# Receiver.net
KiCad netlist of a schematic drawn in Altium Designer
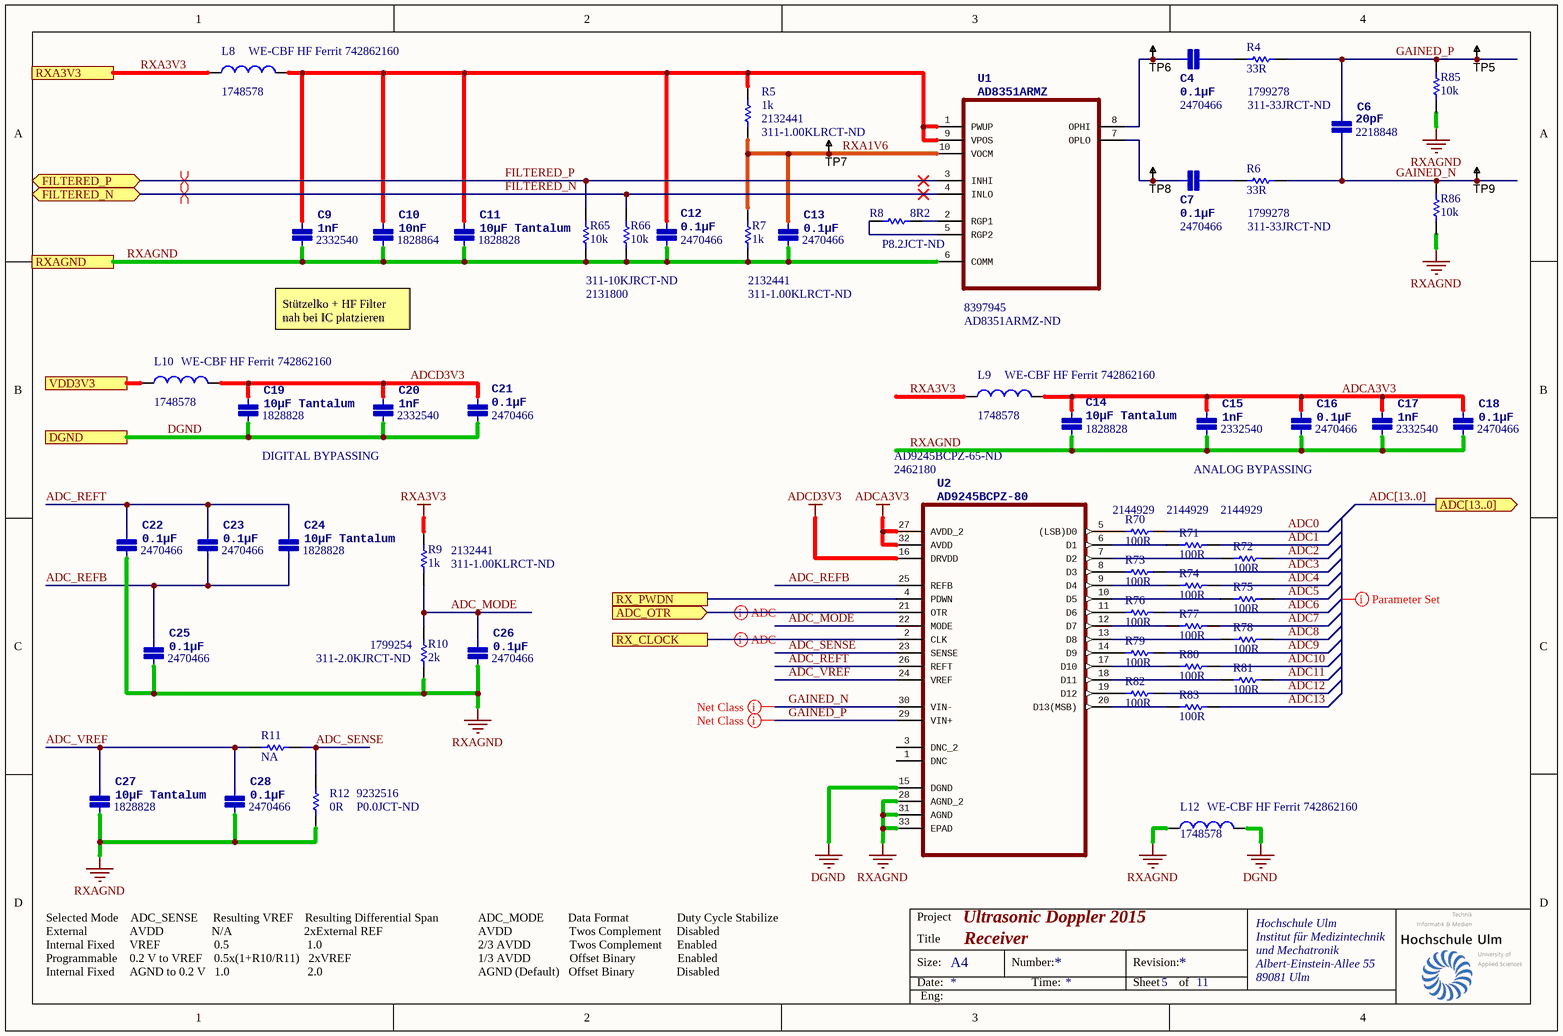
[diagram p0: Receiver.SchDoc]

(export (version "E")
  (design (tool "Eeschema 10.0.6"))
  (components
    (comp (ref "C4")
      (value "0.1µF")
      (footprint "0402[1005]")
      (description "Cap")
      (fields (field (name "SUPPLIER PART NUMBER 1") "2470466"))
      (libsource (lib "") (part "Capacitor_1"))
    )
    (comp (ref "C6")
      (value "20pF")
      (footprint "0402[1005]")
      (description "Cap")
      (fields (field (name "SUPPLIER PART NUMBER 1") "2218848"))
      (libsource (lib "Components") (part "Capacitor"))
    )
    (comp (ref "C7")
      (value "0.1µF")
      (footprint "0402[1005]")
      (description "Cap")
      (fields (field (name "SUPPLIER PART NUMBER 1") "2470466"))
      (libsource (lib "") (part "Capacitor_1"))
    )
    (comp (ref "C9")
      (value "1nF")
      (footprint "0402[1005]")
      (description "Cap")
      (fields (field (name "SUPPLIER PART NUMBER 1") "2332540"))
      (libsource (lib "Components") (part "Capacitor"))
    )
    (comp (ref "C10")
      (value "10nF")
      (footprint "0402[1005]")
      (description "Cap")
      (fields (field (name "SUPPLIER PART NUMBER 1") "1828864"))
      (libsource (lib "Components") (part "Capacitor"))
    )
    (comp (ref "C11")
      (value "10µF Tantalum")
      (footprint "0805[2012]")
      (description "Cap")
      (fields (field (name "SUPPLIER PART NUMBER 1") "1828828"))
      (libsource (lib "Components") (part "Capacitor"))
    )
    (comp (ref "C12")
      (value "0.1µF")
      (footprint "0402[1005]")
      (description "Cap")
      (fields (field (name "SUPPLIER PART NUMBER 1") "2470466"))
      (libsource (lib "Components") (part "Capacitor"))
    )
    (comp (ref "C13")
      (value "0.1µF")
      (footprint "0402[1005]")
      (description "Cap")
      (fields (field (name "SUPPLIER PART NUMBER 1") "2470466"))
      (libsource (lib "Components") (part "Capacitor"))
    )
    (comp (ref "C14")
      (value "10µF Tantalum")
      (footprint "0805[2012]")
      (description "Cap")
      (fields (field (name "SUPPLIER PART NUMBER 1") "1828828"))
      (libsource (lib "Components") (part "Capacitor"))
    )
    (comp (ref "C15")
      (value "1nF")
      (footprint "0402[1005]")
      (description "Cap")
      (fields (field (name "SUPPLIER PART NUMBER 1") "2332540"))
      (libsource (lib "Components") (part "Capacitor"))
    )
    (comp (ref "C16")
      (value "0.1µF")
      (footprint "0402[1005]")
      (description "Cap")
      (fields (field (name "SUPPLIER PART NUMBER 1") "2470466"))
      (libsource (lib "Components") (part "Capacitor"))
    )
    (comp (ref "C17")
      (value "1nF")
      (footprint "0402[1005]")
      (description "Cap")
      (fields (field (name "SUPPLIER PART NUMBER 1") "2332540"))
      (libsource (lib "Components") (part "Capacitor"))
    )
    (comp (ref "C18")
      (value "0.1µF")
      (footprint "0402[1005]")
      (description "Cap")
      (fields (field (name "SUPPLIER PART NUMBER 1") "2470466"))
      (libsource (lib "Components") (part "Capacitor"))
    )
    (comp (ref "C19")
      (value "10µF Tantalum")
      (footprint "0805[2012]")
      (description "Cap")
      (fields (field (name "SUPPLIER PART NUMBER 1") "1828828"))
      (libsource (lib "Components") (part "Capacitor"))
    )
    (comp (ref "C20")
      (value "1nF")
      (footprint "0402[1005]")
      (description "Cap")
      (fields (field (name "SUPPLIER PART NUMBER 1") "2332540"))
      (libsource (lib "Components") (part "Capacitor"))
    )
    (comp (ref "C21")
      (value "0.1µF")
      (footprint "0402[1005]")
      (description "Cap")
      (fields (field (name "SUPPLIER PART NUMBER 1") "2470466"))
      (libsource (lib "Components") (part "Capacitor"))
    )
    (comp (ref "C22")
      (value "0.1µF")
      (footprint "0402[1005]")
      (description "Cap")
      (fields (field (name "SUPPLIER PART NUMBER 1") "2470466"))
      (libsource (lib "Components") (part "Capacitor"))
    )
    (comp (ref "C23")
      (value "0.1µF")
      (footprint "0402[1005]")
      (description "Cap")
      (fields (field (name "SUPPLIER PART NUMBER 1") "2470466"))
      (libsource (lib "Components") (part "Capacitor"))
    )
    (comp (ref "C24")
      (value "10µF Tantalum")
      (footprint "0805[2012]")
      (description "Cap")
      (fields (field (name "SUPPLIER PART NUMBER 1") "1828828"))
      (libsource (lib "Components") (part "Capacitor"))
    )
    (comp (ref "C25")
      (value "0.1µF")
      (footprint "0402[1005]")
      (description "Cap")
      (fields (field (name "SUPPLIER PART NUMBER 1") "2470466"))
      (libsource (lib "Components") (part "Capacitor"))
    )
    (comp (ref "C26")
      (value "0.1µF")
      (footprint "0402[1005]")
      (description "Cap")
      (fields (field (name "SUPPLIER PART NUMBER 1") "2470466"))
      (libsource (lib "Components") (part "Capacitor"))
    )
    (comp (ref "C27")
      (value "10µF Tantalum")
      (footprint "0805[2012]")
      (description "Cap")
      (fields (field (name "SUPPLIER PART NUMBER 1") "1828828"))
      (libsource (lib "Components") (part "Capacitor"))
    )
    (comp (ref "C28")
      (value "0.1µF")
      (footprint "0402[1005]")
      (description "Cap")
      (fields (field (name "SUPPLIER PART NUMBER 1") "2470466"))
      (libsource (lib "Components") (part "Capacitor"))
    )
    (comp (ref "L8")
      (value "WE-CBF HF Ferrit 742862160")
      (footprint "0603[1508]")
      (description "Inductor")
      (fields (field (name "SUPPLIER PART NUMBER 1") "1748578") (field (name "PUBLISHER") "Altium Limited"))
      (libsource (lib "USD Parts") (part "Inductor"))
    )
    (comp (ref "L9")
      (value "WE-CBF HF Ferrit 742862160")
      (footprint "0603[1508]")
      (description "Inductor")
      (fields (field (name "SUPPLIER PART NUMBER 1") "1748578") (field (name "PUBLISHER") "Altium Limited"))
      (libsource (lib "USD Parts") (part "Inductor"))
    )
    (comp (ref "L10")
      (value "WE-CBF HF Ferrit 742862160")
      (footprint "0603[1508]")
      (description "Inductor")
      (fields (field (name "SUPPLIER PART NUMBER 1") "1748578") (field (name "PUBLISHER") "Altium Limited"))
      (libsource (lib "USD Parts") (part "Inductor"))
    )
    (comp (ref "L12")
      (value "WE-CBF HF Ferrit 742862160")
      (footprint "0603[1508]")
      (description "Inductor")
      (fields (field (name "SUPPLIER PART NUMBER 1") "1748578") (field (name "PUBLISHER") "Altium Limited"))
      (libsource (lib "USD Parts") (part "Inductor"))
    )
    (comp (ref "R4")
      (value "33R")
      (footprint "0402[1005]")
      (description "Resistor")
      (fields
        (field (name "SUPPLIER PART NUMBER 1") "311-33JRCT-ND")
        (field (name "SUPPLIER PART NUMBER 2") "1799278")
        (field (name "PUBLISHER") "Altium Limited")
      )
      (libsource (lib "Components") (part "Resistor"))
    )
    (comp (ref "R5")
      (value "1k")
      (footprint "0402[1005]")
      (description "Resistor")
      (fields
        (field (name "SUPPLIER PART NUMBER 1") "311-1.00KLRCT-ND")
        (field (name "SUPPLIER PART NUMBER 2") "2132441")
        (field (name "PUBLISHER") "Altium Limited")
      )
      (libsource (lib "Components") (part "Resistor"))
    )
    (comp (ref "R6")
      (value "33R")
      (footprint "0402[1005]")
      (description "Resistor")
      (fields
        (field (name "SUPPLIER PART NUMBER 1") "311-33JRCT-ND")
        (field (name "SUPPLIER PART NUMBER 2") "1799278")
        (field (name "PUBLISHER") "Altium Limited")
      )
      (libsource (lib "Components") (part "Resistor"))
    )
    (comp (ref "R7")
      (value "1k")
      (footprint "0402[1005]")
      (description "Resistor")
      (fields
        (field (name "SUPPLIER PART NUMBER 1") "311-1.00KLRCT-ND")
        (field (name "SUPPLIER PART NUMBER 2") "2132441")
        (field (name "PUBLISHER") "Altium Limited")
      )
      (libsource (lib "Components") (part "Resistor"))
    )
    (comp (ref "R8")
      (value "8R2")
      (footprint "0402[1005]")
      (description "Resistor")
      (fields
        (field (name "SUPPLIER PART NUMBER 1") "P8.2JCT-ND")
        (field (name "PUBLISHER") "Altium Limited")
      )
      (libsource (lib "Components") (part "Resistor"))
    )
    (comp (ref "R9")
      (value "1k")
      (footprint "0402[1005]")
      (description "Resistor")
      (fields
        (field (name "SUPPLIER PART NUMBER 1") "311-1.00KLRCT-ND")
        (field (name "SUPPLIER PART NUMBER 2") "2132441")
        (field (name "PUBLISHER") "Altium Limited")
      )
      (libsource (lib "Components") (part "Resistor"))
    )
    (comp (ref "R10")
      (value "2k")
      (footprint "0402[1005]")
      (description "Resistor")
      (fields
        (field (name "SUPPLIER PART NUMBER 1") "311-2.0KJRCT-ND")
        (field (name "SUPPLIER PART NUMBER 2") "1799254")
        (field (name "PUBLISHER") "Altium Limited")
      )
      (libsource (lib "Components") (part "Resistor"))
    )
    (comp (ref "R11")
      (value "NA")
      (footprint "0402[1005]")
      (description "Resistor")
      (fields (field (name "PUBLISHER") "Altium Limited"))
      (libsource (lib "Components") (part "Resistor"))
    )
    (comp (ref "R12")
      (value "0R")
      (footprint "0402[1005]")
      (description "Resistor")
      (fields
        (field (name "SUPPLIER PART NUMBER 1") "P0.0JCT-ND")
        (field (name "SUPPLIER PART NUMBER 2") "9232516")
        (field (name "PUBLISHER") "Altium Limited")
      )
      (libsource (lib "Components") (part "Resistor"))
    )
    (comp (ref "R65")
      (value "10k")
      (footprint "0402[1005]")
      (description "Resistor")
      (fields
        (field (name "SUPPLIER PART NUMBER 1") "311-10KJRCT-ND")
        (field (name "SUPPLIER PART NUMBER 2") "2131800")
        (field (name "PUBLISHER") "Altium Limited")
      )
      (libsource (lib "Components") (part "Resistor"))
    )
    (comp (ref "R66")
      (value "10k")
      (footprint "0402[1005]")
      (description "Resistor")
      (fields (field (name "PUBLISHER") "Altium Limited"))
      (libsource (lib "Components") (part "Resistor"))
    )
    (comp (ref "R70")
      (value "100R")
      (footprint "0402[1005]")
      (description "Resistor")
      (fields (field (name "SUPPLIER PART NUMBER 1") "2144929") (field (name "PUBLISHER") "Altium Limited"))
      (libsource (lib "USD Parts") (part "Resistor"))
    )
    (comp (ref "R71")
      (value "100R")
      (footprint "0402[1005]")
      (description "Resistor")
      (fields (field (name "SUPPLIER PART NUMBER 1") "2144929") (field (name "PUBLISHER") "Altium Limited"))
      (libsource (lib "USD Parts") (part "Resistor"))
    )
    (comp (ref "R72")
      (value "100R")
      (footprint "0402[1005]")
      (description "Resistor")
      (fields (field (name "SUPPLIER PART NUMBER 1") "2144929") (field (name "PUBLISHER") "Altium Limited"))
      (libsource (lib "USD Parts") (part "Resistor"))
    )
    (comp (ref "R73")
      (value "100R")
      (footprint "0402[1005]")
      (description "Resistor")
      (fields (field (name "PUBLISHER") "Altium Limited"))
      (libsource (lib "USD Parts") (part "Resistor"))
    )
    (comp (ref "R74")
      (value "100R")
      (footprint "0402[1005]")
      (description "Resistor")
      (fields (field (name "PUBLISHER") "Altium Limited"))
      (libsource (lib "USD Parts") (part "Resistor"))
    )
    (comp (ref "R75")
      (value "100R")
      (footprint "0402[1005]")
      (description "Resistor")
      (fields (field (name "PUBLISHER") "Altium Limited"))
      (libsource (lib "USD Parts") (part "Resistor"))
    )
    (comp (ref "R76")
      (value "100R")
      (footprint "0402[1005]")
      (description "Resistor")
      (fields (field (name "PUBLISHER") "Altium Limited"))
      (libsource (lib "USD Parts") (part "Resistor"))
    )
    (comp (ref "R77")
      (value "100R")
      (footprint "0402[1005]")
      (description "Resistor")
      (fields (field (name "PUBLISHER") "Altium Limited"))
      (libsource (lib "USD Parts") (part "Resistor"))
    )
    (comp (ref "R78")
      (value "100R")
      (footprint "0402[1005]")
      (description "Resistor")
      (fields (field (name "PUBLISHER") "Altium Limited"))
      (libsource (lib "USD Parts") (part "Resistor"))
    )
    (comp (ref "R79")
      (value "100R")
      (footprint "0402[1005]")
      (description "Resistor")
      (fields (field (name "PUBLISHER") "Altium Limited"))
      (libsource (lib "USD Parts") (part "Resistor"))
    )
    (comp (ref "R80")
      (value "100R")
      (footprint "0402[1005]")
      (description "Resistor")
      (fields (field (name "PUBLISHER") "Altium Limited"))
      (libsource (lib "USD Parts") (part "Resistor"))
    )
    (comp (ref "R81")
      (value "100R")
      (footprint "0402[1005]")
      (description "Resistor")
      (fields (field (name "PUBLISHER") "Altium Limited"))
      (libsource (lib "USD Parts") (part "Resistor"))
    )
    (comp (ref "R82")
      (value "100R")
      (footprint "0402[1005]")
      (description "Resistor")
      (fields (field (name "PUBLISHER") "Altium Limited"))
      (libsource (lib "USD Parts") (part "Resistor"))
    )
    (comp (ref "R83")
      (value "100R")
      (footprint "0402[1005]")
      (description "Resistor")
      (fields (field (name "PUBLISHER") "Altium Limited"))
      (libsource (lib "USD Parts") (part "Resistor"))
    )
    (comp (ref "R85")
      (value "10k")
      (footprint "0402[1005]")
      (description "Resistor")
      (fields (field (name "PUBLISHER") "Altium Limited"))
      (libsource (lib "Components") (part "Resistor"))
    )
    (comp (ref "R86")
      (value "10k")
      (footprint "0402[1005]")
      (description "Resistor")
      (fields (field (name "PUBLISHER") "Altium Limited"))
      (libsource (lib "Components") (part "Resistor"))
    )
    (comp (ref "TP5")
      (value "TESTPOINT_THT_MINI")
      (footprint "TP-THT-MINI")
      (description "Test Point PCB mount Miniature White")
      (fields (field (name "PBL PART NUMBER") "3100-567"))
      (libsource (lib "USD Parts") (part "TESTPOINT_THT_MINI"))
    )
    (comp (ref "TP6")
      (value "TESTPOINT_THT_MINI")
      (footprint "TP-THT-MINI")
      (description "Test Point PCB mount Miniature White")
      (fields (field (name "PBL PART NUMBER") "3100-567"))
      (libsource (lib "USD Parts") (part "TESTPOINT_THT_MINI"))
    )
    (comp (ref "TP7")
      (value "TESTPOINT")
      (footprint "TP-R60")
      (description "SMD test pin")
      (libsource (lib "USD Parts") (part "TESTPOINT"))
    )
    (comp (ref "TP8")
      (value "TESTPOINT_THT_MINI")
      (footprint "TP-THT-MINI")
      (description "Test Point PCB mount Miniature White")
      (fields (field (name "PBL PART NUMBER") "3100-567"))
      (libsource (lib "USD Parts") (part "TESTPOINT_THT_MINI"))
    )
    (comp (ref "TP9")
      (value "TESTPOINT_THT_MINI")
      (footprint "TP-THT-MINI")
      (description "Test Point PCB mount Miniature White")
      (fields (field (name "PBL PART NUMBER") "3100-567"))
      (libsource (lib "USD Parts") (part "TESTPOINT_THT_MINI"))
    )
    (comp (ref "U1")
      (value "AD8351ARMZ")
      (footprint "MSOP10")
      (description "Differential RF/IF Amplifier")
      (fields
        (field (name "SUPPLIER PART NUMBER 1") "AD8351ARMZ-ND")
        (field (name "SUPPLIER PART NUMBER 2") "8397945")
      )
      (libsource (lib "Components") (part "AD8351ARMZ"))
    )
    (comp (ref "U2")
      (value "AD9245BCPZ-80")
      (footprint "LFCSP-32")
      (description "DIFF 14-Bit ADC")
      (fields
        (field (name "SUPPLIER PART NUMBER 1") "2462180")
        (field (name "SUPPLIER PART NUMBER 2") "AD9245BCPZ-65-ND")
      )
      (libsource (lib "Components") (part "AD9245BCPZ-80"))
    )
  )
  (nets
    (net (code "1") (name "/ADC0") (class "Default")
      (node (ref "R70") (pin "2") (pinfunction "2_2") (pintype "passive"))
    )
    (net (code "2") (name "/ADC1") (class "Default")
      (node (ref "R71") (pin "2") (pinfunction "2_2") (pintype "passive"))
    )
    (net (code "3") (name "/ADC2") (class "Default")
      (node (ref "R72") (pin "2") (pinfunction "2_2") (pintype "passive"))
    )
    (net (code "4") (name "/ADC3") (class "Default")
      (node (ref "R73") (pin "2") (pinfunction "2_2") (pintype "passive"))
    )
    (net (code "5") (name "/ADC4") (class "Default")
      (node (ref "R74") (pin "2") (pinfunction "2_2") (pintype "passive"))
    )
    (net (code "6") (name "/ADC5") (class "Default")
      (node (ref "R75") (pin "2") (pinfunction "2_2") (pintype "passive"))
    )
    (net (code "7") (name "/ADC6") (class "Default")
      (node (ref "R76") (pin "2") (pinfunction "2_2") (pintype "passive"))
    )
    (net (code "8") (name "/ADC7") (class "Default")
      (node (ref "R77") (pin "2") (pinfunction "2_2") (pintype "passive"))
    )
    (net (code "9") (name "/ADC8") (class "Default")
      (node (ref "R78") (pin "2") (pinfunction "2_2") (pintype "passive"))
    )
    (net (code "10") (name "/ADC9") (class "Default")
      (node (ref "R79") (pin "2") (pinfunction "2_2") (pintype "passive"))
    )
    (net (code "11") (name "/ADC10") (class "Default")
      (node (ref "R80") (pin "2") (pinfunction "2_2") (pintype "passive"))
    )
    (net (code "12") (name "/ADC11") (class "Default")
      (node (ref "R81") (pin "2") (pinfunction "2_2") (pintype "passive"))
    )
    (net (code "13") (name "/ADC12") (class "Default")
      (node (ref "R82") (pin "2") (pinfunction "2_2") (pintype "passive"))
    )
    (net (code "14") (name "/ADC13") (class "Default")
      (node (ref "R83") (pin "2") (pinfunction "2_2") (pintype "passive"))
    )
    (net (code "16") (name "/ADC_MODE") (class "Default")
      (node (ref "C26") (pin "1") (pinfunction "P$1_1") (pintype "passive"))
      (node (ref "R10") (pin "1") (pinfunction "1_1") (pintype "passive"))
      (node (ref "R9") (pin "2") (pinfunction "2_2") (pintype "passive"))
      (node (ref "U2") (pin "22") (pinfunction "MODE_22") (pintype "passive"))
    )
    (net (code "17") (name "/ADC_OTR") (class "Default")
      (node (ref "U2") (pin "21") (pinfunction "OTR_21") (pintype "passive"))
    )
    (net (code "18") (name "/ADC_REFB") (class "Default")
      (node (ref "C23") (pin "2") (pinfunction "P$2_2") (pintype "passive"))
      (node (ref "C24") (pin "2") (pinfunction "P$2_2") (pintype "passive"))
      (node (ref "C25") (pin "1") (pinfunction "P$1_1") (pintype "passive"))
      (node (ref "U2") (pin "25") (pinfunction "REFB_25") (pintype "passive"))
    )
    (net (code "19") (name "/ADC_REFT") (class "Default")
      (node (ref "C22") (pin "1") (pinfunction "P$1_1") (pintype "passive"))
      (node (ref "C23") (pin "1") (pinfunction "P$1_1") (pintype "passive"))
      (node (ref "C24") (pin "1") (pinfunction "P$1_1") (pintype "passive"))
      (node (ref "U2") (pin "26") (pinfunction "REFT_26") (pintype "passive"))
    )
    (net (code "20") (name "/ADC_SENSE") (class "Default")
      (node (ref "R11") (pin "1") (pinfunction "1_1") (pintype "passive"))
      (node (ref "R12") (pin "1") (pinfunction "1_1") (pintype "passive"))
      (node (ref "U2") (pin "23") (pinfunction "SENSE_23") (pintype "passive"))
    )
    (net (code "21") (name "/ADC_VREF") (class "Default")
      (node (ref "C27") (pin "1") (pinfunction "P$1_1") (pintype "passive"))
      (node (ref "C28") (pin "1") (pinfunction "P$1_1") (pintype "passive"))
      (node (ref "R11") (pin "2") (pinfunction "2_2") (pintype "passive"))
      (node (ref "U2") (pin "24") (pinfunction "VREF_24") (pintype "passive"))
    )
    (net (code "22") (name "/FILTERED_N") (class "Default")
      (node (ref "R66") (pin "1") (pinfunction "1_1") (pintype "passive"))
      (node (ref "U1") (pin "4") (pinfunction "INLO_4") (pintype "passive"))
    )
    (net (code "23") (name "/FILTERED_P") (class "Default")
      (node (ref "R65") (pin "1") (pinfunction "1_1") (pintype "passive"))
      (node (ref "U1") (pin "3") (pinfunction "INHI_3") (pintype "passive"))
    )
    (net (code "24") (name "/GAINED_N") (class "Default")
      (node (ref "C6") (pin "2") (pinfunction "P$2_2") (pintype "passive"))
      (node (ref "R6") (pin "2") (pinfunction "2_2") (pintype "passive"))
      (node (ref "R86") (pin "1") (pinfunction "1_1") (pintype "passive"))
      (node (ref "TP9") (pin "1") (pintype "passive"))
      (node (ref "U2") (pin "30") (pinfunction "VIN-_30") (pintype "passive"))
    )
    (net (code "25") (name "/GAINED_P") (class "Default")
      (node (ref "C6") (pin "1") (pinfunction "P$1_1") (pintype "passive"))
      (node (ref "R4") (pin "2") (pinfunction "2_2") (pintype "passive"))
      (node (ref "R85") (pin "1") (pinfunction "1_1") (pintype "passive"))
      (node (ref "TP5") (pin "1") (pintype "passive"))
      (node (ref "U2") (pin "29") (pinfunction "VIN+_29") (pintype "passive"))
    )
    (net (code "26") (name "/RXA1V6") (class "Default")
      (node (ref "C13") (pin "1") (pinfunction "P$1_1") (pintype "passive"))
      (node (ref "R5") (pin "2") (pinfunction "2_2") (pintype "passive"))
      (node (ref "R7") (pin "1") (pinfunction "1_1") (pintype "passive"))
      (node (ref "TP7") (pin "1") (pintype "passive"))
      (node (ref "U1") (pin "10") (pinfunction "VOCM_10") (pintype "passive"))
    )
    (net (code "27") (name "/RX_CLOCK") (class "Default")
      (node (ref "U2") (pin "2") (pinfunction "CLK_2") (pintype "passive"))
    )
    (net (code "28") (name "/RX_PWDN") (class "Default")
      (node (ref "U2") (pin "4") (pinfunction "PDWN_4") (pintype "passive"))
    )
    (net (code "29") (name "/VDD3V3") (class "Default")
      (node (ref "L10") (pin "1") (pinfunction "1_1") (pintype "passive"))
    )
    (net (code "30") (name "ADCA3V3") (class "Default")
      (node (ref "C14") (pin "1") (pinfunction "P$1_1") (pintype "passive"))
      (node (ref "C15") (pin "1") (pinfunction "P$1_1") (pintype "passive"))
      (node (ref "C16") (pin "1") (pinfunction "P$1_1") (pintype "passive"))
      (node (ref "C17") (pin "1") (pinfunction "P$1_1") (pintype "passive"))
      (node (ref "C18") (pin "1") (pinfunction "P$1_1") (pintype "passive"))
      (node (ref "L9") (pin "2") (pinfunction "2_2") (pintype "passive"))
      (node (ref "U2") (pin "27") (pinfunction "AVDD_2_27") (pintype "power_in"))
      (node (ref "U2") (pin "32") (pinfunction "AVDD_32") (pintype "power_in"))
    )
    (net (code "31") (name "ADCD3V3") (class "Default")
      (node (ref "C19") (pin "1") (pinfunction "P$1_1") (pintype "passive"))
      (node (ref "C20") (pin "1") (pinfunction "P$1_1") (pintype "passive"))
      (node (ref "C21") (pin "1") (pinfunction "P$1_1") (pintype "passive"))
      (node (ref "L10") (pin "2") (pinfunction "2_2") (pintype "passive"))
      (node (ref "U2") (pin "16") (pinfunction "DRVDD_16") (pintype "power_in"))
    )
    (net (code "32") (name "DGND") (class "Default")
      (node (ref "C19") (pin "2") (pinfunction "P$2_2") (pintype "passive"))
      (node (ref "C20") (pin "2") (pinfunction "P$2_2") (pintype "passive"))
      (node (ref "C21") (pin "2") (pinfunction "P$2_2") (pintype "passive"))
      (node (ref "L12") (pin "2") (pinfunction "2_2") (pintype "passive"))
      (node (ref "U2") (pin "15") (pinfunction "DGND_15") (pintype "passive"))
    )
    (net (code "33") (name "Net-(C4-P$1)") (class "Default")
      (node (ref "C4") (pin "1") (pinfunction "P$1_1") (pintype "passive"))
      (node (ref "TP6") (pin "1") (pintype "passive"))
      (node (ref "U1") (pin "8") (pinfunction "OPHI_8") (pintype "passive"))
    )
    (net (code "34") (name "Net-(C4-P$2)") (class "Default")
      (node (ref "C4") (pin "2") (pinfunction "P$2_2") (pintype "passive"))
      (node (ref "R4") (pin "1") (pinfunction "1_1") (pintype "passive"))
    )
    (net (code "35") (name "Net-(C7-P$1)") (class "Default")
      (node (ref "C7") (pin "1") (pinfunction "P$1_1") (pintype "passive"))
      (node (ref "TP8") (pin "1") (pintype "passive"))
      (node (ref "U1") (pin "7") (pinfunction "OPLO_7") (pintype "passive"))
    )
    (net (code "36") (name "Net-(C7-P$2)") (class "Default")
      (node (ref "C7") (pin "2") (pinfunction "P$2_2") (pintype "passive"))
      (node (ref "R6") (pin "1") (pinfunction "1_1") (pintype "passive"))
    )
    (net (code "37") (name "Net-(C10-P$1)") (class "Default")
      (node (ref "C10") (pin "1") (pinfunction "P$1_1") (pintype "passive"))
      (node (ref "C11") (pin "1") (pinfunction "P$1_1") (pintype "passive"))
      (node (ref "C12") (pin "1") (pinfunction "P$1_1") (pintype "passive"))
      (node (ref "C9") (pin "1") (pinfunction "P$1_1") (pintype "passive"))
      (node (ref "L8") (pin "2") (pinfunction "2_2") (pintype "passive"))
      (node (ref "R5") (pin "1") (pinfunction "1_1") (pintype "passive"))
      (node (ref "U1") (pin "1") (pinfunction "PWUP_1") (pintype "passive"))
      (node (ref "U1") (pin "9") (pinfunction "VPOS_9") (pintype "passive"))
    )
    (net (code "38") (name "Net-(U1-RGP1)") (class "Default")
      (node (ref "R8") (pin "1") (pinfunction "1_1") (pintype "passive"))
      (node (ref "U1") (pin "2") (pinfunction "RGP1_2") (pintype "passive"))
    )
    (net (code "39") (name "Net-(U1-RGP2)") (class "Default")
      (node (ref "R8") (pin "2") (pinfunction "2_2") (pintype "passive"))
      (node (ref "U1") (pin "5") (pinfunction "RGP2_5") (pintype "passive"))
    )
    (net (code "40") (name "Net-(U2-(LSB)D0)") (class "Default")
      (node (ref "R70") (pin "1") (pinfunction "1_1") (pintype "passive"))
      (node (ref "U2") (pin "5") (pinfunction "(LSB)D0_5") (pintype "output"))
    )
    (net (code "41") (name "Net-(U2-D1)") (class "Default")
      (node (ref "R71") (pin "1") (pinfunction "1_1") (pintype "passive"))
      (node (ref "U2") (pin "6") (pinfunction "D1_6") (pintype "output"))
    )
    (net (code "42") (name "Net-(U2-D2)") (class "Default")
      (node (ref "R72") (pin "1") (pinfunction "1_1") (pintype "passive"))
      (node (ref "U2") (pin "7") (pinfunction "D2_7") (pintype "output"))
    )
    (net (code "43") (name "Net-(U2-D3)") (class "Default")
      (node (ref "R73") (pin "1") (pinfunction "1_1") (pintype "passive"))
      (node (ref "U2") (pin "8") (pinfunction "D3_8") (pintype "output"))
    )
    (net (code "44") (name "Net-(U2-D4)") (class "Default")
      (node (ref "R74") (pin "1") (pinfunction "1_1") (pintype "passive"))
      (node (ref "U2") (pin "9") (pinfunction "D4_9") (pintype "output"))
    )
    (net (code "45") (name "Net-(U2-D5)") (class "Default")
      (node (ref "R75") (pin "1") (pinfunction "1_1") (pintype "passive"))
      (node (ref "U2") (pin "10") (pinfunction "D5_10") (pintype "output"))
    )
    (net (code "46") (name "Net-(U2-D6)") (class "Default")
      (node (ref "R76") (pin "1") (pinfunction "1_1") (pintype "passive"))
      (node (ref "U2") (pin "11") (pinfunction "D6_11") (pintype "output"))
    )
    (net (code "47") (name "Net-(U2-D7)") (class "Default")
      (node (ref "R77") (pin "1") (pinfunction "1_1") (pintype "passive"))
      (node (ref "U2") (pin "12") (pinfunction "D7_12") (pintype "output"))
    )
    (net (code "48") (name "Net-(U2-D8)") (class "Default")
      (node (ref "R78") (pin "1") (pinfunction "1_1") (pintype "passive"))
      (node (ref "U2") (pin "13") (pinfunction "D8_13") (pintype "output"))
    )
    (net (code "49") (name "Net-(U2-D9)") (class "Default")
      (node (ref "R79") (pin "1") (pinfunction "1_1") (pintype "passive"))
      (node (ref "U2") (pin "14") (pinfunction "D9_14") (pintype "output"))
    )
    (net (code "50") (name "Net-(U2-D10)") (class "Default")
      (node (ref "R80") (pin "1") (pinfunction "1_1") (pintype "passive"))
      (node (ref "U2") (pin "17") (pinfunction "D10_17") (pintype "output"))
    )
    (net (code "51") (name "Net-(U2-D11)") (class "Default")
      (node (ref "R81") (pin "1") (pinfunction "1_1") (pintype "passive"))
      (node (ref "U2") (pin "18") (pinfunction "D11_18") (pintype "output"))
    )
    (net (code "52") (name "Net-(U2-D12)") (class "Default")
      (node (ref "R82") (pin "1") (pinfunction "1_1") (pintype "passive"))
      (node (ref "U2") (pin "19") (pinfunction "D12_19") (pintype "output"))
    )
    (net (code "53") (name "Net-(U2-D13(MSB))") (class "Default")
      (node (ref "R83") (pin "1") (pinfunction "1_1") (pintype "passive"))
      (node (ref "U2") (pin "20") (pinfunction "D13(MSB)_20") (pintype "output"))
    )
    (net (code "54") (name "RXA3V3") (class "Default")
      (node (ref "L8") (pin "1") (pinfunction "1_1") (pintype "passive"))
      (node (ref "L9") (pin "1") (pinfunction "1_1") (pintype "passive"))
      (node (ref "R9") (pin "1") (pinfunction "1_1") (pintype "passive"))
    )
    (net (code "55") (name "RXAGND") (class "Default")
      (node (ref "C10") (pin "2") (pinfunction "P$2_2") (pintype "passive"))
      (node (ref "C11") (pin "2") (pinfunction "P$2_2") (pintype "passive"))
      (node (ref "C12") (pin "2") (pinfunction "P$2_2") (pintype "passive"))
      (node (ref "C13") (pin "2") (pinfunction "P$2_2") (pintype "passive"))
      (node (ref "C14") (pin "2") (pinfunction "P$2_2") (pintype "passive"))
      (node (ref "C15") (pin "2") (pinfunction "P$2_2") (pintype "passive"))
      (node (ref "C16") (pin "2") (pinfunction "P$2_2") (pintype "passive"))
      (node (ref "C17") (pin "2") (pinfunction "P$2_2") (pintype "passive"))
      (node (ref "C18") (pin "2") (pinfunction "P$2_2") (pintype "passive"))
      (node (ref "C22") (pin "2") (pinfunction "P$2_2") (pintype "passive"))
      (node (ref "C25") (pin "2") (pinfunction "P$2_2") (pintype "passive"))
      (node (ref "C26") (pin "2") (pinfunction "P$2_2") (pintype "passive"))
      (node (ref "C27") (pin "2") (pinfunction "P$2_2") (pintype "passive"))
      (node (ref "C28") (pin "2") (pinfunction "P$2_2") (pintype "passive"))
      (node (ref "C9") (pin "2") (pinfunction "P$2_2") (pintype "passive"))
      (node (ref "L12") (pin "1") (pinfunction "1_1") (pintype "passive"))
      (node (ref "R10") (pin "2") (pinfunction "2_2") (pintype "passive"))
      (node (ref "R12") (pin "2") (pinfunction "2_2") (pintype "passive"))
      (node (ref "R65") (pin "2") (pinfunction "2_2") (pintype "passive"))
      (node (ref "R66") (pin "2") (pinfunction "2_2") (pintype "passive"))
      (node (ref "R7") (pin "2") (pinfunction "2_2") (pintype "passive"))
      (node (ref "R85") (pin "2") (pinfunction "2_2") (pintype "passive"))
      (node (ref "R86") (pin "2") (pinfunction "2_2") (pintype "passive"))
      (node (ref "U1") (pin "6") (pinfunction "COMM_6") (pintype "passive"))
      (node (ref "U2") (pin "28") (pinfunction "AGND_2_28") (pintype "passive"))
      (node (ref "U2") (pin "31") (pinfunction "AGND_31") (pintype "passive"))
      (node (ref "U2") (pin "33") (pinfunction "EPAD_33") (pintype "passive"))
    )
    (net (code "56") (name "unconnected-(U2-DNC-Pad1)") (class "Default")
      (node (ref "U2") (pin "1") (pinfunction "DNC_1") (pintype "passive"))
    )
    (net (code "57") (name "unconnected-(U2-DNC_2-Pad3)") (class "Default")
      (node (ref "U2") (pin "3") (pinfunction "DNC_2_3") (pintype "passive"))
    )
  )
)
